# FPGA_10_100_Ethernet_PHY.net
KiCad netlist of a schematic drawn in Altium Designer
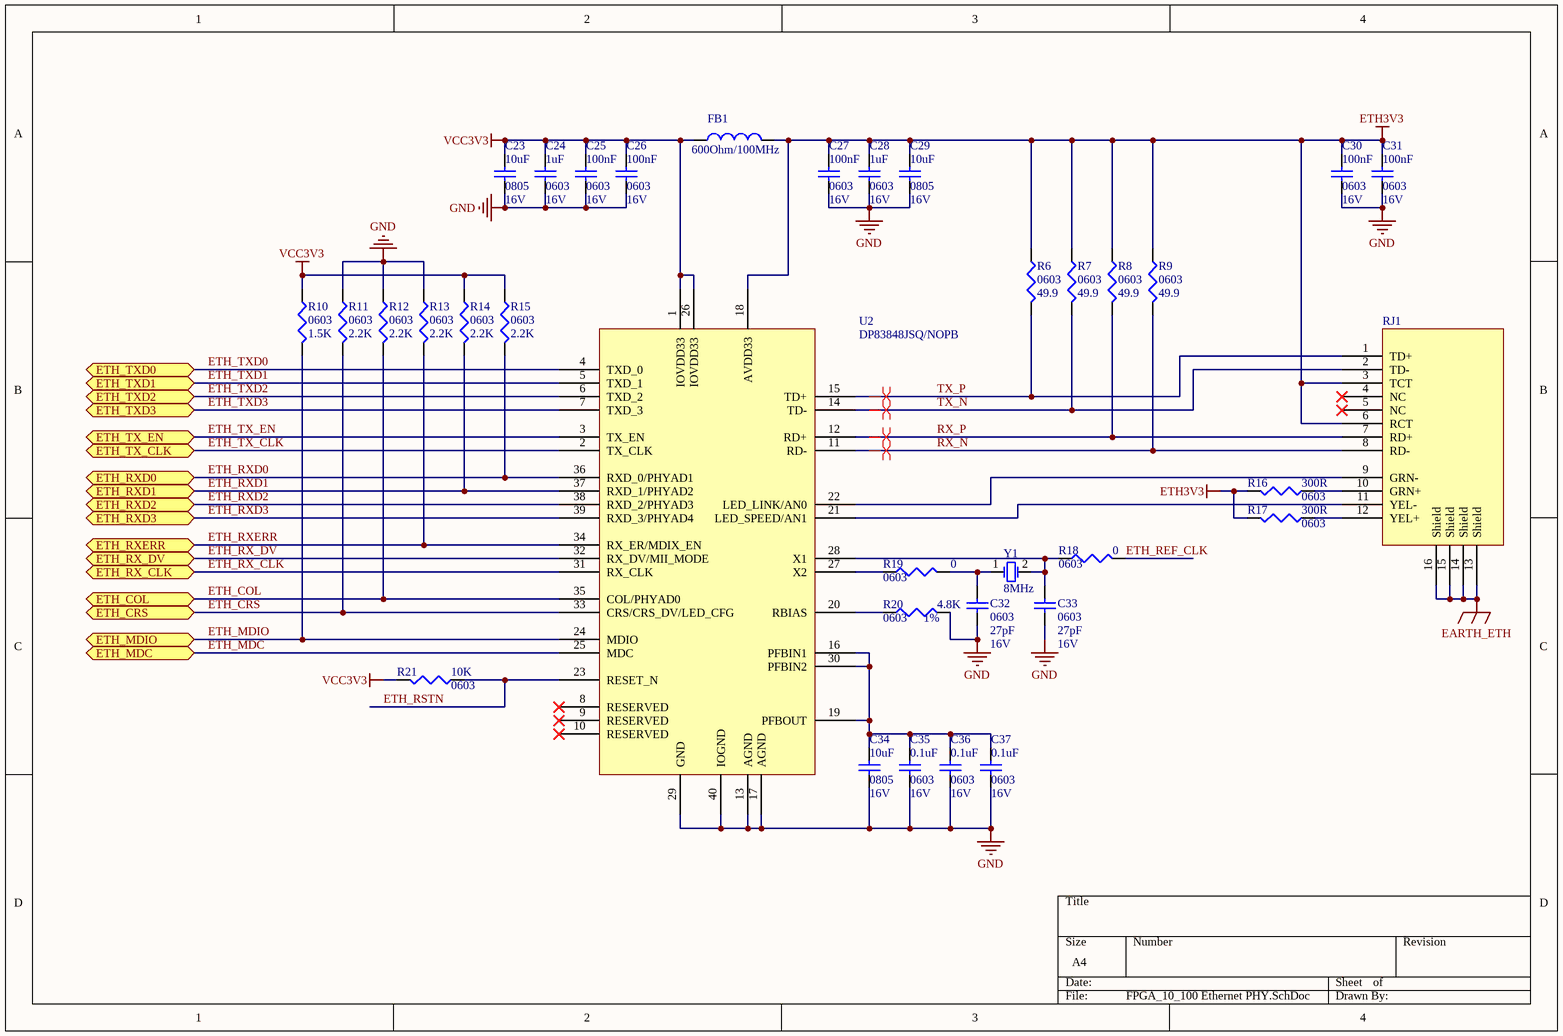
[diagram p0: FPGA_10_100 Ethernet PHY.SchDoc]

(export (version "E")
  (design (tool "Eeschema 10.0.6"))
  (components
    (comp (ref "C23")
      (value "10uF")
      (footprint "2012[0805]")
      (description "Capacitor (Semiconductor SIM Model)")
      (fields
        (field (name "PACKAGEREFERENCE") "0805")
        (field (name "V") "16V")
        (field (name "PUBLISHER") "Altium Limited")
      )
      (libsource (lib "Devices") (part "Cap Semi"))
    )
    (comp (ref "C24")
      (value "1uF")
      (footprint "1608[0603]")
      (description "Capacitor (Semiconductor SIM Model)")
      (fields
        (field (name "PACKAGEREFERENCE") "0603")
        (field (name "V") "16V")
        (field (name "PUBLISHER") "Altium Limited")
      )
      (libsource (lib "Devices") (part "Cap Semi"))
    )
    (comp (ref "C25")
      (value "100nF")
      (footprint "1608[0603]")
      (description "Capacitor (Semiconductor SIM Model)")
      (fields
        (field (name "PACKAGEREFERENCE") "0603")
        (field (name "V") "16V")
        (field (name "PUBLISHER") "Altium Limited")
      )
      (libsource (lib "Devices") (part "Cap Semi"))
    )
    (comp (ref "C26")
      (value "100nF")
      (footprint "1608[0603]")
      (description "Capacitor (Semiconductor SIM Model)")
      (fields
        (field (name "PACKAGEREFERENCE") "0603")
        (field (name "V") "16V")
        (field (name "PUBLISHER") "Altium Limited")
      )
      (libsource (lib "Devices") (part "Cap Semi"))
    )
    (comp (ref "C27")
      (value "100nF")
      (footprint "1608[0603]")
      (description "Capacitor (Semiconductor SIM Model)")
      (fields
        (field (name "PACKAGEREFERENCE") "0603")
        (field (name "V") "16V")
        (field (name "PUBLISHER") "Altium Limited")
      )
      (libsource (lib "Devices") (part "Cap Semi"))
    )
    (comp (ref "C28")
      (value "1uF")
      (footprint "1608[0603]")
      (description "Capacitor (Semiconductor SIM Model)")
      (fields
        (field (name "PACKAGEREFERENCE") "0603")
        (field (name "V") "16V")
        (field (name "PUBLISHER") "Altium Limited")
      )
      (libsource (lib "Devices") (part "Cap Semi"))
    )
    (comp (ref "C29")
      (value "10uF")
      (footprint "2012[0805]")
      (description "Capacitor (Semiconductor SIM Model)")
      (fields
        (field (name "PACKAGEREFERENCE") "0805")
        (field (name "V") "16V")
        (field (name "PUBLISHER") "Altium Limited")
      )
      (libsource (lib "Devices") (part "Cap Semi"))
    )
    (comp (ref "C30")
      (value "100nF")
      (footprint "1608[0603]")
      (description "Capacitor (Semiconductor SIM Model)")
      (fields
        (field (name "PACKAGEREFERENCE") "0603")
        (field (name "V") "16V")
        (field (name "PUBLISHER") "Altium Limited")
      )
      (libsource (lib "Devices") (part "Cap Semi"))
    )
    (comp (ref "C31")
      (value "100nF")
      (footprint "1608[0603]")
      (description "Capacitor (Semiconductor SIM Model)")
      (fields
        (field (name "PACKAGEREFERENCE") "0603")
        (field (name "V") "16V")
        (field (name "PUBLISHER") "Altium Limited")
      )
      (libsource (lib "Devices") (part "Cap Semi"))
    )
    (comp (ref "C32")
      (value "27pF")
      (footprint "1608[0603]")
      (description "Capacitor (Semiconductor SIM Model)")
      (fields
        (field (name "PACKAGEREFERENCE") "0603")
        (field (name "V") "16V")
        (field (name "PUBLISHER") "Altium Limited")
      )
      (libsource (lib "Devices") (part "Cap Semi"))
    )
    (comp (ref "C33")
      (value "27pF")
      (footprint "1608[0603]")
      (description "Capacitor (Semiconductor SIM Model)")
      (fields
        (field (name "PACKAGEREFERENCE") "0603")
        (field (name "V") "16V")
        (field (name "PUBLISHER") "Altium Limited")
      )
      (libsource (lib "Devices") (part "Cap Semi"))
    )
    (comp (ref "C34")
      (value "10uF")
      (footprint "2012[0805]")
      (description "Capacitor (Semiconductor SIM Model)")
      (fields
        (field (name "PACKAGEREFERENCE") "0805")
        (field (name "V") "16V")
        (field (name "PUBLISHER") "Altium Limited")
      )
      (libsource (lib "Devices") (part "Cap Semi"))
    )
    (comp (ref "C35")
      (value "0.1uF")
      (footprint "1608[0603]")
      (description "Capacitor (Semiconductor SIM Model)")
      (fields
        (field (name "PACKAGEREFERENCE") "0603")
        (field (name "V") "16V")
        (field (name "PUBLISHER") "Altium Limited")
      )
      (libsource (lib "Devices") (part "Cap Semi"))
    )
    (comp (ref "C36")
      (value "0.1uF")
      (footprint "1608[0603]")
      (description "Capacitor (Semiconductor SIM Model)")
      (fields
        (field (name "PACKAGEREFERENCE") "0603")
        (field (name "V") "16V")
        (field (name "PUBLISHER") "Altium Limited")
      )
      (libsource (lib "Devices") (part "Cap Semi"))
    )
    (comp (ref "C37")
      (value "0.1uF")
      (footprint "1608[0603]")
      (description "Capacitor (Semiconductor SIM Model)")
      (fields
        (field (name "PACKAGEREFERENCE") "0603")
        (field (name "V") "16V")
        (field (name "PUBLISHER") "Altium Limited")
      )
      (libsource (lib "Devices") (part "Cap Semi"))
    )
    (comp (ref "FB1")
      (value "600Ohm/100MHz")
      (footprint "2012[0805]")
      (description "Inductor")
      (libsource (lib "Miscellaneous Devices") (part "Inductor"))
    )
    (comp (ref "R6")
      (value "49.9")
      (footprint "1608[0603]")
      (description "Resistor")
      (fields
        (field (name "PACKAGEREFERENCE") "0603")
        (field (name "Comment") "Res3")
        (field (name "PUBLISHER") "Altium Limited")
      )
      (libsource (lib "Miscellaneous Devices") (part "Res3"))
    )
    (comp (ref "R7")
      (value "49.9")
      (footprint "1608[0603]")
      (description "Resistor")
      (fields
        (field (name "PACKAGEREFERENCE") "0603")
        (field (name "Comment") "Res3")
        (field (name "PUBLISHER") "Altium Limited")
      )
      (libsource (lib "Miscellaneous Devices") (part "Res3"))
    )
    (comp (ref "R8")
      (value "49.9")
      (footprint "1608[0603]")
      (description "Resistor")
      (fields
        (field (name "PACKAGEREFERENCE") "0603")
        (field (name "Comment") "Res3")
        (field (name "PUBLISHER") "Altium Limited")
      )
      (libsource (lib "Miscellaneous Devices") (part "Res3"))
    )
    (comp (ref "R9")
      (value "49.9")
      (footprint "1608[0603]")
      (description "Resistor")
      (fields
        (field (name "PACKAGEREFERENCE") "0603")
        (field (name "Comment") "Res3")
        (field (name "PUBLISHER") "Altium Limited")
      )
      (libsource (lib "Miscellaneous Devices") (part "Res3"))
    )
    (comp (ref "R10")
      (value "1.5K")
      (footprint "1608[0603]")
      (description "Resistor")
      (fields
        (field (name "PACKAGEREFERENCE") "0603")
        (field (name "Comment") "Res3")
        (field (name "PUBLISHER") "Altium Limited")
      )
      (libsource (lib "Miscellaneous Devices") (part "Res3"))
    )
    (comp (ref "R11")
      (value "2.2K")
      (footprint "1608[0603]")
      (description "Resistor")
      (fields
        (field (name "PACKAGEREFERENCE") "0603")
        (field (name "Comment") "Res3")
        (field (name "PUBLISHER") "Altium Limited")
      )
      (libsource (lib "Miscellaneous Devices") (part "Res3"))
    )
    (comp (ref "R12")
      (value "2.2K")
      (footprint "1608[0603]")
      (description "Resistor")
      (fields
        (field (name "PACKAGEREFERENCE") "0603")
        (field (name "Comment") "Res3")
        (field (name "PUBLISHER") "Altium Limited")
      )
      (libsource (lib "Miscellaneous Devices") (part "Res3"))
    )
    (comp (ref "R13")
      (value "2.2K")
      (footprint "1608[0603]")
      (description "Resistor")
      (fields
        (field (name "PACKAGEREFERENCE") "0603")
        (field (name "Comment") "Res3")
        (field (name "PUBLISHER") "Altium Limited")
      )
      (libsource (lib "Miscellaneous Devices") (part "Res3"))
    )
    (comp (ref "R14")
      (value "2.2K")
      (footprint "1608[0603]")
      (description "Resistor")
      (fields
        (field (name "PACKAGEREFERENCE") "0603")
        (field (name "Comment") "Res3")
        (field (name "PUBLISHER") "Altium Limited")
      )
      (libsource (lib "Miscellaneous Devices") (part "Res3"))
    )
    (comp (ref "R15")
      (value "2.2K")
      (footprint "1608[0603]")
      (description "Resistor")
      (fields
        (field (name "PACKAGEREFERENCE") "0603")
        (field (name "Comment") "Res3")
        (field (name "PUBLISHER") "Altium Limited")
      )
      (libsource (lib "Miscellaneous Devices") (part "Res3"))
    )
    (comp (ref "R16")
      (value "300R")
      (footprint "1608[0603]")
      (description "Resistor")
      (fields
        (field (name "PACKAGEREFERENCE") "0603")
        (field (name "Comment") "Res3")
        (field (name "PUBLISHER") "Altium Limited")
      )
      (libsource (lib "Miscellaneous Devices") (part "Res3"))
    )
    (comp (ref "R17")
      (value "300R")
      (footprint "1608[0603]")
      (description "Resistor")
      (fields
        (field (name "PACKAGEREFERENCE") "0603")
        (field (name "Comment") "Res3")
        (field (name "PUBLISHER") "Altium Limited")
      )
      (libsource (lib "Miscellaneous Devices") (part "Res3"))
    )
    (comp (ref "R18")
      (value "0")
      (footprint "1608[0603]")
      (description "Resistor")
      (fields
        (field (name "PACKAGEREFERENCE") "0603")
        (field (name "Comment") "Res3")
        (field (name "PUBLISHER") "Altium Limited")
      )
      (libsource (lib "Miscellaneous Devices") (part "Res3"))
    )
    (comp (ref "R19")
      (value "0")
      (footprint "1608[0603]")
      (description "Resistor")
      (fields
        (field (name "PACKAGEREFERENCE") "0603")
        (field (name "Comment") "Res3")
        (field (name "PUBLISHER") "Altium Limited")
      )
      (libsource (lib "Miscellaneous Devices") (part "Res3"))
    )
    (comp (ref "R20")
      (value "4.8K")
      (footprint "1608[0603]")
      (description "Resistor")
      (fields
        (field (name "PACKAGEREFERENCE") "0603")
        (field (name "AC") "1%")
        (field (name "Comment") "Res3")
        (field (name "PUBLISHER") "Altium Limited")
      )
      (libsource (lib "Miscellaneous Devices") (part "Res3"))
    )
    (comp (ref "R21")
      (value "10K")
      (footprint "1608[0603]")
      (description "Resistor")
      (fields
        (field (name "PACKAGEREFERENCE") "0603")
        (field (name "Comment") "Res3")
        (field (name "PUBLISHER") "Altium Limited")
      )
      (libsource (lib "Miscellaneous Devices") (part "Res3"))
    )
    (comp (ref "RJ1")
      (value "RJ45")
      (footprint "RJ45-1")
      (description "网口座")
      (libsource (lib "DLH") (part "RJ45"))
    )
    (comp (ref "U2")
      (value "DP83848JSQ/NOPB")
      (footprint "DP83848J")
      (libsource (lib "Spartan6_LX9_A0") (part "DP83848JSQ/NOPB"))
    )
    (comp (ref "Y1")
      (value "8MHz")
      (footprint "XTAL_A")
      (description "Crystal Oscillator")
      (fields (field (name "PUBLISHER") "Altium Limited"))
      (libsource (lib "Devices") (part "XTAL"))
    )
  )
  (nets
    (net (code "1") (name "/ETH_COL") (class "Default")
      (node (ref "R12") (pin "2") (pinfunction "2_2") (pintype "passive"))
      (node (ref "U2") (pin "35") (pinfunction "COL/PHYAD0_35") (pintype "passive"))
    )
    (net (code "2") (name "/ETH_CRS") (class "Default")
      (node (ref "R11") (pin "2") (pinfunction "2_2") (pintype "passive"))
      (node (ref "U2") (pin "33") (pinfunction "CRS/CRS_DV/LED_CFG_33") (pintype "passive"))
    )
    (net (code "3") (name "/ETH_MDC") (class "Default")
      (node (ref "U2") (pin "25") (pinfunction "MDC_25") (pintype "passive"))
    )
    (net (code "4") (name "/ETH_MDIO") (class "Default")
      (node (ref "R10") (pin "2") (pinfunction "2_2") (pintype "passive"))
      (node (ref "U2") (pin "24") (pinfunction "MDIO_24") (pintype "passive"))
    )
    (net (code "5") (name "/ETH_REF_CLK") (class "Default")
      (node (ref "R18") (pin "2") (pinfunction "2_2") (pintype "passive"))
    )
    (net (code "6") (name "/ETH_RSTN") (class "Default")
      (node (ref "R21") (pin "1") (pinfunction "1_1") (pintype "passive"))
      (node (ref "U2") (pin "23") (pinfunction "RESET_N_23") (pintype "passive"))
    )
    (net (code "7") (name "/ETH_RXD0") (class "Default")
      (node (ref "R15") (pin "2") (pinfunction "2_2") (pintype "passive"))
      (node (ref "U2") (pin "36") (pinfunction "RXD_0/PHYAD1_36") (pintype "passive"))
    )
    (net (code "8") (name "/ETH_RXD1") (class "Default")
      (node (ref "R14") (pin "2") (pinfunction "2_2") (pintype "passive"))
      (node (ref "U2") (pin "37") (pinfunction "RXD_1/PHYAD2_37") (pintype "passive"))
    )
    (net (code "9") (name "/ETH_RXD2") (class "Default")
      (node (ref "U2") (pin "38") (pinfunction "RXD_2/PHYAD3_38") (pintype "passive"))
    )
    (net (code "10") (name "/ETH_RXD3") (class "Default")
      (node (ref "U2") (pin "39") (pinfunction "RXD_3/PHYAD4_39") (pintype "passive"))
    )
    (net (code "11") (name "/ETH_RXERR") (class "Default")
      (node (ref "R13") (pin "2") (pinfunction "2_2") (pintype "passive"))
      (node (ref "U2") (pin "34") (pinfunction "RX_ER/MDIX_EN_34") (pintype "passive"))
    )
    (net (code "12") (name "/ETH_RX_CLK") (class "Default")
      (node (ref "U2") (pin "31") (pinfunction "RX_CLK_31") (pintype "passive"))
    )
    (net (code "13") (name "/ETH_RX_DV") (class "Default")
      (node (ref "U2") (pin "32") (pinfunction "RX_DV/MII_MODE_32") (pintype "passive"))
    )
    (net (code "14") (name "/ETH_TXD0") (class "Default")
      (node (ref "U2") (pin "4") (pinfunction "TXD_0_4") (pintype "passive"))
    )
    (net (code "15") (name "/ETH_TXD1") (class "Default")
      (node (ref "U2") (pin "5") (pinfunction "TXD_1_5") (pintype "passive"))
    )
    (net (code "16") (name "/ETH_TXD2") (class "Default")
      (node (ref "U2") (pin "6") (pinfunction "TXD_2_6") (pintype "passive"))
    )
    (net (code "17") (name "/ETH_TXD3") (class "Default")
      (node (ref "U2") (pin "7") (pinfunction "TXD_3_7") (pintype "passive"))
    )
    (net (code "18") (name "/ETH_TX_CLK") (class "Default")
      (node (ref "U2") (pin "2") (pinfunction "TX_CLK_2") (pintype "passive"))
    )
    (net (code "19") (name "/ETH_TX_EN") (class "Default")
      (node (ref "U2") (pin "3") (pinfunction "TX_EN_3") (pintype "passive"))
    )
    (net (code "20") (name "/RX_N") (class "Default")
      (node (ref "R9") (pin "2") (pinfunction "2_2") (pintype "passive"))
      (node (ref "RJ1") (pin "8") (pinfunction "RD-_8") (pintype "passive"))
      (node (ref "U2") (pin "11") (pinfunction "RD-_11") (pintype "passive"))
    )
    (net (code "21") (name "/RX_P") (class "Default")
      (node (ref "R8") (pin "2") (pinfunction "2_2") (pintype "passive"))
      (node (ref "RJ1") (pin "7") (pinfunction "RD+_7") (pintype "passive"))
      (node (ref "U2") (pin "12") (pinfunction "RD+_12") (pintype "passive"))
    )
    (net (code "22") (name "/TX_N") (class "Default")
      (node (ref "R7") (pin "2") (pinfunction "2_2") (pintype "passive"))
      (node (ref "RJ1") (pin "2") (pinfunction "TD-_2") (pintype "passive"))
      (node (ref "U2") (pin "14") (pinfunction "TD-_14") (pintype "passive"))
    )
    (net (code "23") (name "/TX_P") (class "Default")
      (node (ref "R6") (pin "2") (pinfunction "2_2") (pintype "passive"))
      (node (ref "RJ1") (pin "1") (pinfunction "TD+_1") (pintype "passive"))
      (node (ref "U2") (pin "15") (pinfunction "TD+_15") (pintype "passive"))
    )
    (net (code "24") (name "EARTH_ETH") (class "Default")
      (node (ref "RJ1") (pin "13") (pinfunction "Shield_13") (pintype "passive"))
      (node (ref "RJ1") (pin "14") (pinfunction "Shield_14") (pintype "passive"))
      (node (ref "RJ1") (pin "15") (pinfunction "Shield_15") (pintype "passive"))
      (node (ref "RJ1") (pin "16") (pinfunction "Shield_16") (pintype "passive"))
    )
    (net (code "25") (name "ETH3V3") (class "Default")
      (node (ref "C27") (pin "1") (pinfunction "1_1") (pintype "passive"))
      (node (ref "C28") (pin "1") (pinfunction "1_1") (pintype "passive"))
      (node (ref "C29") (pin "1") (pinfunction "1_1") (pintype "passive"))
      (node (ref "C30") (pin "1") (pinfunction "1_1") (pintype "passive"))
      (node (ref "C31") (pin "1") (pinfunction "1_1") (pintype "passive"))
      (node (ref "FB1") (pin "2") (pinfunction "2_2") (pintype "passive"))
      (node (ref "R16") (pin "2") (pinfunction "2_2") (pintype "passive"))
      (node (ref "R17") (pin "2") (pinfunction "2_2") (pintype "passive"))
      (node (ref "R6") (pin "1") (pinfunction "1_1") (pintype "passive"))
      (node (ref "R7") (pin "1") (pinfunction "1_1") (pintype "passive"))
      (node (ref "R8") (pin "1") (pinfunction "1_1") (pintype "passive"))
      (node (ref "R9") (pin "1") (pinfunction "1_1") (pintype "passive"))
      (node (ref "RJ1") (pin "3") (pinfunction "TCT_3") (pintype "passive"))
      (node (ref "RJ1") (pin "6") (pinfunction "RCT_6") (pintype "passive"))
      (node (ref "U2") (pin "18") (pinfunction "AVDD33_18") (pintype "passive"))
    )
    (net (code "26") (name "GND") (class "Default")
      (node (ref "C23") (pin "2") (pinfunction "2_2") (pintype "passive"))
      (node (ref "C24") (pin "2") (pinfunction "2_2") (pintype "passive"))
      (node (ref "C25") (pin "2") (pinfunction "2_2") (pintype "passive"))
      (node (ref "C26") (pin "2") (pinfunction "2_2") (pintype "passive"))
      (node (ref "C27") (pin "2") (pinfunction "2_2") (pintype "passive"))
      (node (ref "C28") (pin "2") (pinfunction "2_2") (pintype "passive"))
      (node (ref "C29") (pin "2") (pinfunction "2_2") (pintype "passive"))
      (node (ref "C30") (pin "2") (pinfunction "2_2") (pintype "passive"))
      (node (ref "C31") (pin "2") (pinfunction "2_2") (pintype "passive"))
      (node (ref "C32") (pin "2") (pinfunction "2_2") (pintype "passive"))
      (node (ref "C33") (pin "2") (pinfunction "2_2") (pintype "passive"))
      (node (ref "C34") (pin "2") (pinfunction "2_2") (pintype "passive"))
      (node (ref "C35") (pin "2") (pinfunction "2_2") (pintype "passive"))
      (node (ref "C36") (pin "2") (pinfunction "2_2") (pintype "passive"))
      (node (ref "C37") (pin "2") (pinfunction "2_2") (pintype "passive"))
      (node (ref "R11") (pin "1") (pinfunction "1_1") (pintype "passive"))
      (node (ref "R12") (pin "1") (pinfunction "1_1") (pintype "passive"))
      (node (ref "R13") (pin "1") (pinfunction "1_1") (pintype "passive"))
      (node (ref "R20") (pin "2") (pinfunction "2_2") (pintype "passive"))
      (node (ref "U2") (pin "13") (pinfunction "AGND_13") (pintype "passive"))
      (node (ref "U2") (pin "17") (pinfunction "AGND_17") (pintype "passive"))
      (node (ref "U2") (pin "29") (pinfunction "GND_29") (pintype "passive"))
      (node (ref "U2") (pin "40") (pinfunction "IOGND_40") (pintype "passive"))
    )
    (net (code "27") (name "Net-(RJ1-GRN+)") (class "Default")
      (node (ref "R16") (pin "1") (pinfunction "1_1") (pintype "passive"))
      (node (ref "RJ1") (pin "10") (pinfunction "GRN+_10") (pintype "passive"))
    )
    (net (code "28") (name "Net-(RJ1-GRN-)") (class "Default")
      (node (ref "RJ1") (pin "9") (pinfunction "GRN-_9") (pintype "passive"))
      (node (ref "U2") (pin "22") (pinfunction "LED_LINK/AN0_22") (pintype "passive"))
    )
    (net (code "29") (name "Net-(RJ1-YEL+)") (class "Default")
      (node (ref "R17") (pin "1") (pinfunction "1_1") (pintype "passive"))
      (node (ref "RJ1") (pin "12") (pinfunction "YEL+_12") (pintype "passive"))
    )
    (net (code "30") (name "Net-(RJ1-YEL-)") (class "Default")
      (node (ref "RJ1") (pin "11") (pinfunction "YEL-_11") (pintype "passive"))
      (node (ref "U2") (pin "21") (pinfunction "LED_SPEED/AN1_21") (pintype "passive"))
    )
    (net (code "31") (name "Net-(U2-PFBIN1)") (class "Default")
      (node (ref "C34") (pin "1") (pinfunction "1_1") (pintype "passive"))
      (node (ref "C35") (pin "1") (pinfunction "1_1") (pintype "passive"))
      (node (ref "C36") (pin "1") (pinfunction "1_1") (pintype "passive"))
      (node (ref "C37") (pin "1") (pinfunction "1_1") (pintype "passive"))
      (node (ref "U2") (pin "16") (pinfunction "PFBIN1_16") (pintype "passive"))
      (node (ref "U2") (pin "19") (pinfunction "PFBOUT_19") (pintype "passive"))
      (node (ref "U2") (pin "30") (pinfunction "PFBIN2_30") (pintype "passive"))
    )
    (net (code "32") (name "Net-(U2-RBIAS)") (class "Default")
      (node (ref "R20") (pin "1") (pinfunction "1_1") (pintype "passive"))
      (node (ref "U2") (pin "20") (pinfunction "RBIAS_20") (pintype "passive"))
    )
    (net (code "33") (name "Net-(U2-X1)") (class "Default")
      (node (ref "C33") (pin "1") (pinfunction "1_1") (pintype "passive"))
      (node (ref "R18") (pin "1") (pinfunction "1_1") (pintype "passive"))
      (node (ref "U2") (pin "28") (pinfunction "X1_28") (pintype "passive"))
      (node (ref "Y1") (pin "2") (pinfunction "OSC2_2") (pintype "passive"))
    )
    (net (code "34") (name "Net-(U2-X2)") (class "Default")
      (node (ref "R19") (pin "1") (pinfunction "1_1") (pintype "passive"))
      (node (ref "U2") (pin "27") (pinfunction "X2_27") (pintype "passive"))
    )
    (net (code "35") (name "Net-(Y1-OSC1)") (class "Default")
      (node (ref "C32") (pin "1") (pinfunction "1_1") (pintype "passive"))
      (node (ref "R19") (pin "2") (pinfunction "2_2") (pintype "passive"))
      (node (ref "Y1") (pin "1") (pinfunction "OSC1_1") (pintype "passive"))
    )
    (net (code "36") (name "VCC3V3") (class "Default")
      (node (ref "C23") (pin "1") (pinfunction "1_1") (pintype "passive"))
      (node (ref "C24") (pin "1") (pinfunction "1_1") (pintype "passive"))
      (node (ref "C25") (pin "1") (pinfunction "1_1") (pintype "passive"))
      (node (ref "C26") (pin "1") (pinfunction "1_1") (pintype "passive"))
      (node (ref "FB1") (pin "1") (pinfunction "1_1") (pintype "passive"))
      (node (ref "R10") (pin "1") (pinfunction "1_1") (pintype "passive"))
      (node (ref "R14") (pin "1") (pinfunction "1_1") (pintype "passive"))
      (node (ref "R15") (pin "1") (pinfunction "1_1") (pintype "passive"))
      (node (ref "R21") (pin "2") (pinfunction "2_2") (pintype "passive"))
      (node (ref "U2") (pin "1") (pinfunction "IOVDD33_1") (pintype "passive"))
      (node (ref "U2") (pin "26") (pinfunction "IOVDD33_26") (pintype "passive"))
    )
    (net (code "37") (name "unconnected-(RJ1-NC-Pad4)") (class "Default")
      (node (ref "RJ1") (pin "4") (pinfunction "NC_4") (pintype "passive+no_connect"))
    )
    (net (code "38") (name "unconnected-(RJ1-NC-Pad5)") (class "Default")
      (node (ref "RJ1") (pin "5") (pinfunction "NC_5") (pintype "passive+no_connect"))
    )
    (net (code "39") (name "unconnected-(U2-RESERVED-Pad8)") (class "Default")
      (node (ref "U2") (pin "8") (pinfunction "RESERVED_8") (pintype "passive+no_connect"))
    )
    (net (code "40") (name "unconnected-(U2-RESERVED-Pad9)") (class "Default")
      (node (ref "U2") (pin "9") (pinfunction "RESERVED_9") (pintype "passive+no_connect"))
    )
    (net (code "41") (name "unconnected-(U2-RESERVED-Pad10)") (class "Default")
      (node (ref "U2") (pin "10") (pinfunction "RESERVED_10") (pintype "passive+no_connect"))
    )
  )
)
